# Nappe2_0___Pannelized_3.net
KiCad netlist of a schematic drawn in EAGLE
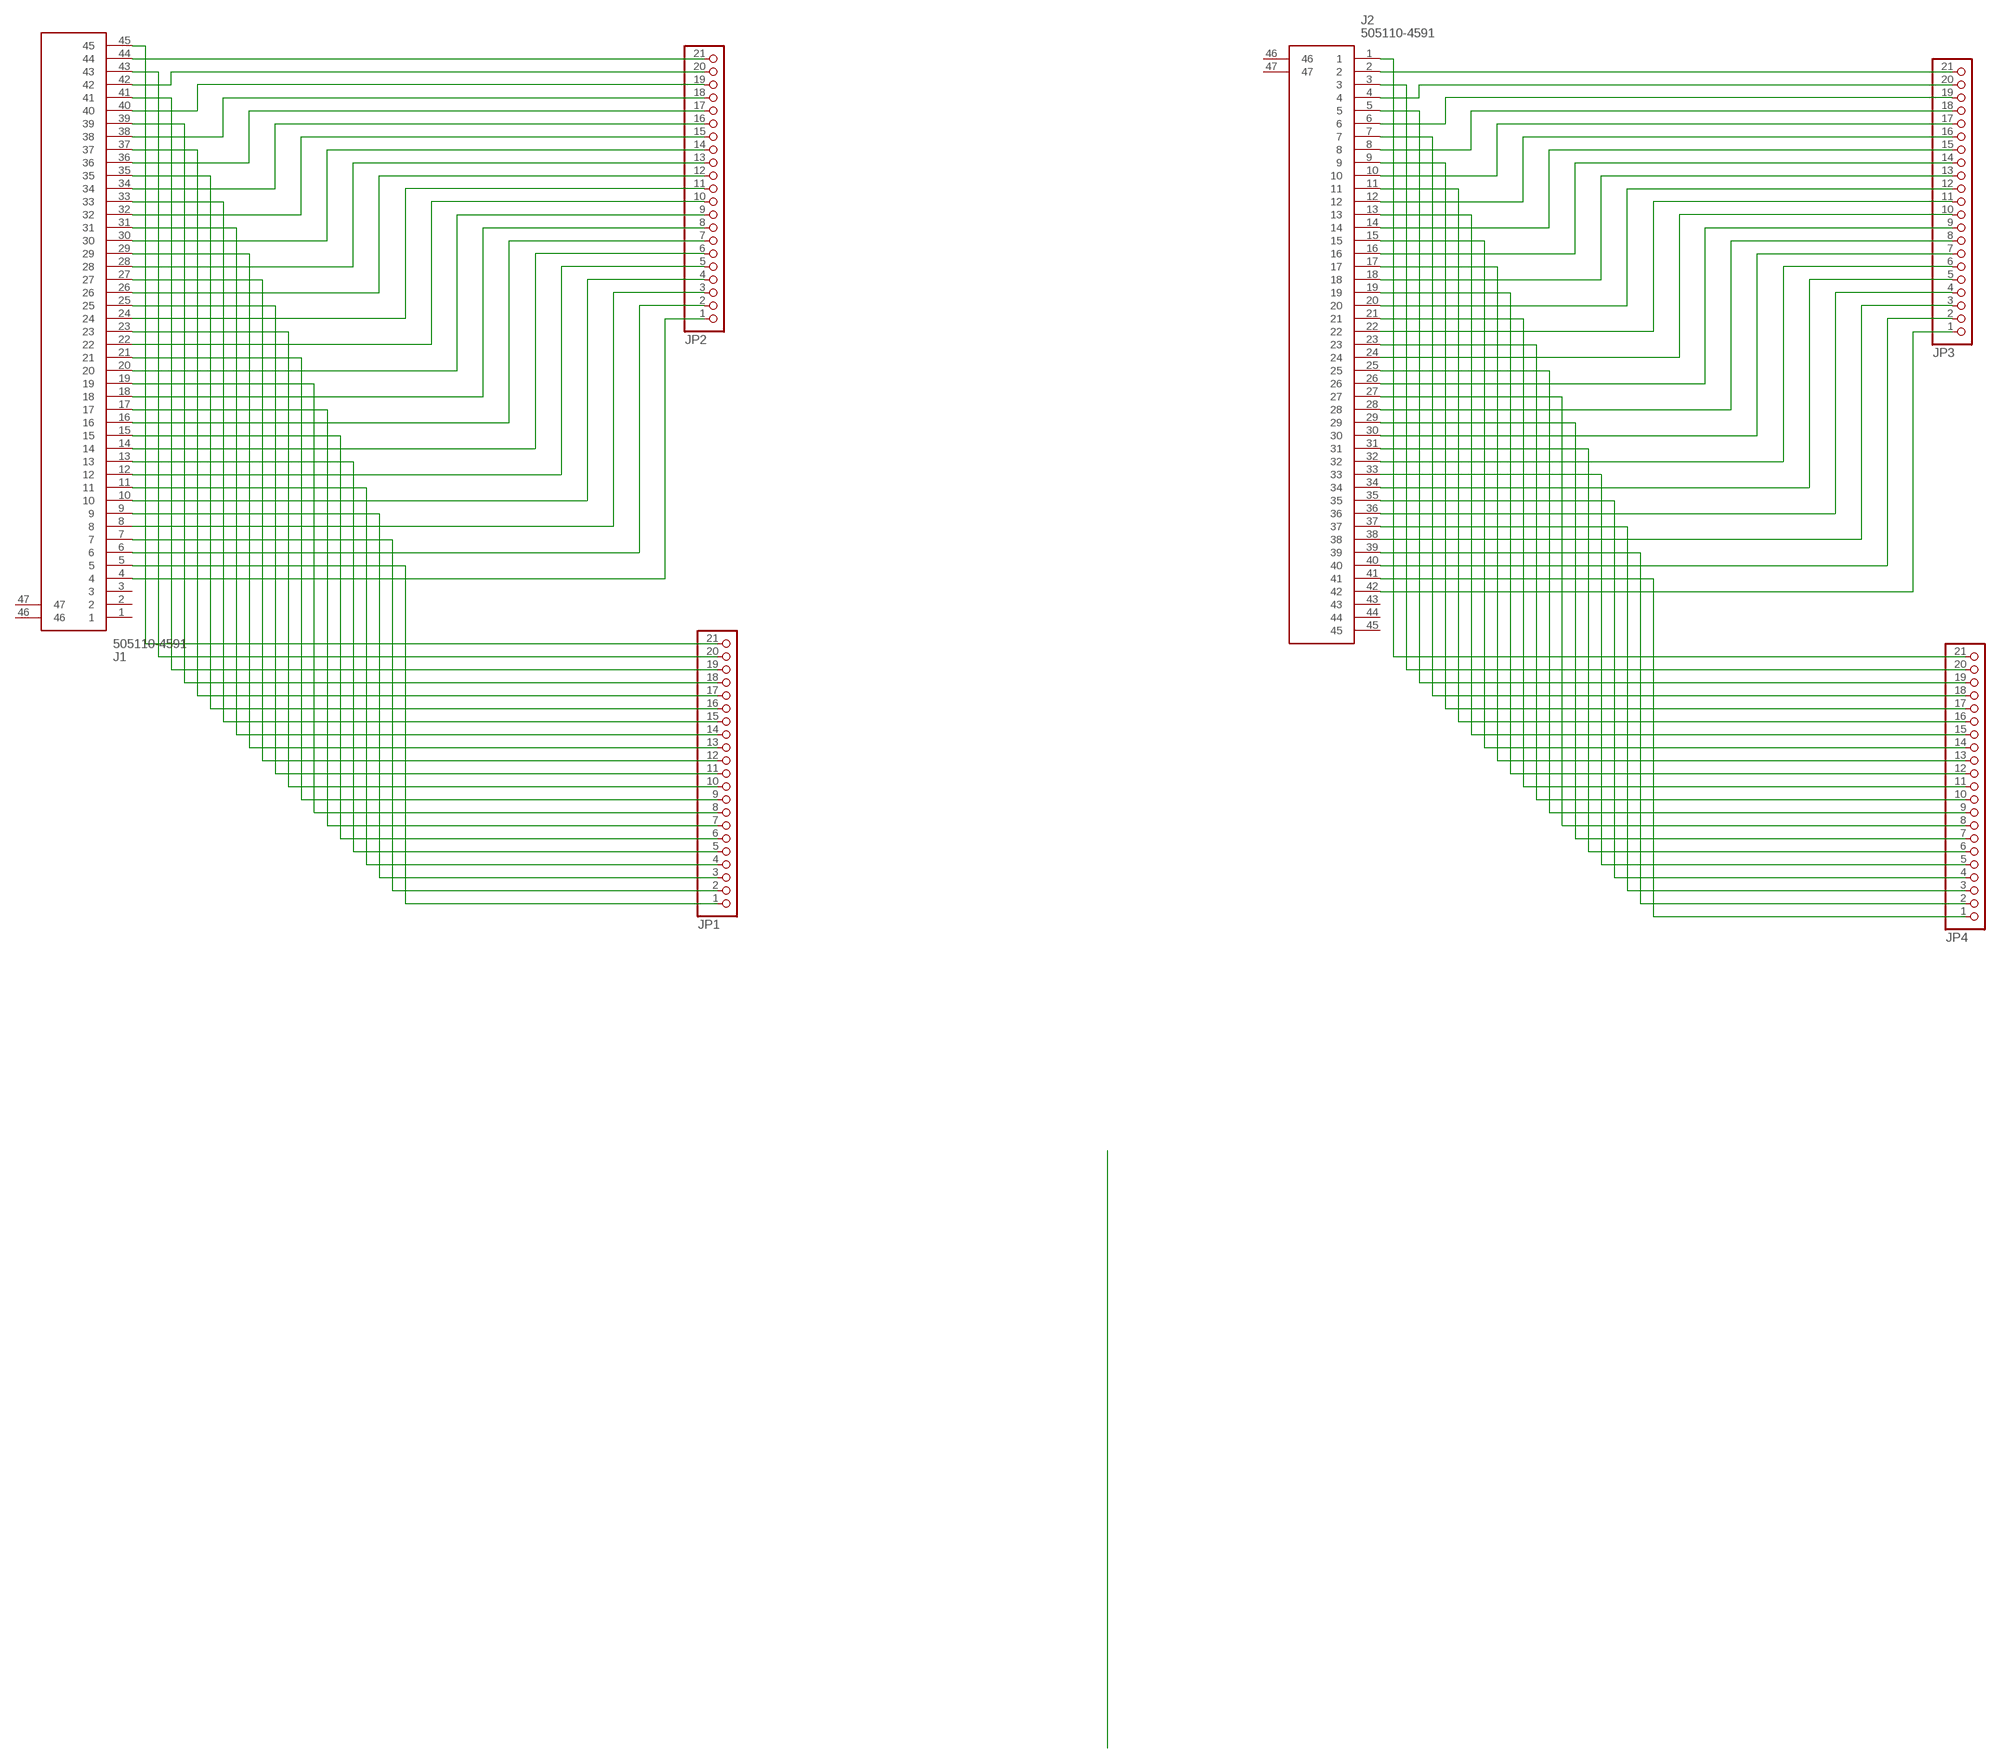
[diagram p0: schematic, sheet 1]

(export (version "E")
  (design (tool "Eeschema 10.0.6"))
  (components
    (comp (ref "J1")
      (value "505110-4591")
      (footprint "eagle-import:5051104591")
      (fields (field (name "MOUSER_PART_NUMBER") "538-505110-4591"))
      (libsource (lib "eagle-import") (part "505110-4591"))
    )
    (comp (ref "J2")
      (value "505110-4591")
      (footprint "eagle-import:5051104591")
      (fields (field (name "MOUSER_PART_NUMBER") "538-505110-4591"))
      (libsource (lib "eagle-import") (part "505110-4591"))
    )
    (comp (ref "JP1")
      (value "PINHD-1X21(2.4)")
      (footprint "eagle-import:1X21(2.4)")
      (libsource (lib "eagle-import") (part "PINHD-1X21(2.4)"))
    )
    (comp (ref "JP2")
      (value "PINHD-1X21(2.4)")
      (footprint "eagle-import:1X21(2.4)")
      (libsource (lib "eagle-import") (part "PINHD-1X21(2.4)"))
    )
    (comp (ref "JP3")
      (value "PINHD-1X21(2.4)")
      (footprint "eagle-import:1X21(2.4)")
      (libsource (lib "eagle-import") (part "PINHD-1X21(2.4)"))
    )
    (comp (ref "JP4")
      (value "PINHD-1X21(2.4)")
      (footprint "eagle-import:1X21(2.4)")
      (libsource (lib "eagle-import") (part "PINHD-1X21(2.4)"))
    )
  )
  (nets
    (net (code "1") (name "Net-(J1-Pad4)") (class "Default")
      (node (ref "J1") (pin "4") (pinfunction "4_4") (pintype "bidirectional"))
      (node (ref "JP2") (pin "1") (pinfunction "1_1") (pintype "passive"))
    )
    (net (code "2") (name "Net-(J1-Pad5)") (class "Default")
      (node (ref "J1") (pin "5") (pinfunction "5_5") (pintype "bidirectional"))
      (node (ref "JP1") (pin "1") (pinfunction "1_1") (pintype "passive"))
    )
    (net (code "3") (name "Net-(J1-Pad6)") (class "Default")
      (node (ref "J1") (pin "6") (pinfunction "6_6") (pintype "bidirectional"))
      (node (ref "JP2") (pin "2") (pinfunction "2_2") (pintype "passive"))
    )
    (net (code "4") (name "Net-(J1-Pad7)") (class "Default")
      (node (ref "J1") (pin "7") (pinfunction "7_7") (pintype "bidirectional"))
      (node (ref "JP1") (pin "2") (pinfunction "2_2") (pintype "passive"))
    )
    (net (code "5") (name "Net-(J1-Pad8)") (class "Default")
      (node (ref "J1") (pin "8") (pinfunction "8_8") (pintype "bidirectional"))
      (node (ref "JP2") (pin "3") (pinfunction "3_3") (pintype "passive"))
    )
    (net (code "6") (name "Net-(J1-Pad9)") (class "Default")
      (node (ref "J1") (pin "9") (pinfunction "9_9") (pintype "bidirectional"))
      (node (ref "JP1") (pin "3") (pinfunction "3_3") (pintype "passive"))
    )
    (net (code "7") (name "Net-(J1-Pad10)") (class "Default")
      (node (ref "J1") (pin "10") (pinfunction "10_10") (pintype "bidirectional"))
      (node (ref "JP2") (pin "4") (pinfunction "4_4") (pintype "passive"))
    )
    (net (code "8") (name "Net-(J1-Pad11)") (class "Default")
      (node (ref "J1") (pin "11") (pinfunction "11_11") (pintype "bidirectional"))
      (node (ref "JP1") (pin "4") (pinfunction "4_4") (pintype "passive"))
    )
    (net (code "9") (name "Net-(J1-Pad12)") (class "Default")
      (node (ref "J1") (pin "12") (pinfunction "12_12") (pintype "bidirectional"))
      (node (ref "JP2") (pin "5") (pinfunction "5_5") (pintype "passive"))
    )
    (net (code "10") (name "Net-(J1-Pad13)") (class "Default")
      (node (ref "J1") (pin "13") (pinfunction "13_13") (pintype "bidirectional"))
      (node (ref "JP1") (pin "5") (pinfunction "5_5") (pintype "passive"))
    )
    (net (code "11") (name "Net-(J1-Pad14)") (class "Default")
      (node (ref "J1") (pin "14") (pinfunction "14_14") (pintype "bidirectional"))
      (node (ref "JP2") (pin "6") (pinfunction "6_6") (pintype "passive"))
    )
    (net (code "12") (name "Net-(J1-Pad15)") (class "Default")
      (node (ref "J1") (pin "15") (pinfunction "15_15") (pintype "bidirectional"))
      (node (ref "JP1") (pin "6") (pinfunction "6_6") (pintype "passive"))
    )
    (net (code "13") (name "Net-(J1-Pad16)") (class "Default")
      (node (ref "J1") (pin "16") (pinfunction "16_16") (pintype "bidirectional"))
      (node (ref "JP2") (pin "7") (pinfunction "7_7") (pintype "passive"))
    )
    (net (code "14") (name "Net-(J1-Pad17)") (class "Default")
      (node (ref "J1") (pin "17") (pinfunction "17_17") (pintype "bidirectional"))
      (node (ref "JP1") (pin "7") (pinfunction "7_7") (pintype "passive"))
    )
    (net (code "15") (name "Net-(J1-Pad18)") (class "Default")
      (node (ref "J1") (pin "18") (pinfunction "18_18") (pintype "bidirectional"))
      (node (ref "JP2") (pin "8") (pinfunction "8_8") (pintype "passive"))
    )
    (net (code "16") (name "Net-(J1-Pad19)") (class "Default")
      (node (ref "J1") (pin "19") (pinfunction "19_19") (pintype "bidirectional"))
      (node (ref "JP1") (pin "8") (pinfunction "8_8") (pintype "passive"))
    )
    (net (code "17") (name "Net-(J1-Pad20)") (class "Default")
      (node (ref "J1") (pin "20") (pinfunction "20_20") (pintype "bidirectional"))
      (node (ref "JP2") (pin "9") (pinfunction "9_9") (pintype "passive"))
    )
    (net (code "18") (name "Net-(J1-Pad21)") (class "Default")
      (node (ref "J1") (pin "21") (pinfunction "21_21") (pintype "bidirectional"))
      (node (ref "JP1") (pin "9") (pinfunction "9_9") (pintype "passive"))
    )
    (net (code "19") (name "Net-(J1-Pad22)") (class "Default")
      (node (ref "J1") (pin "22") (pinfunction "22_22") (pintype "bidirectional"))
      (node (ref "JP2") (pin "10") (pinfunction "10_10") (pintype "passive"))
    )
    (net (code "20") (name "Net-(J1-Pad23)") (class "Default")
      (node (ref "J1") (pin "23") (pinfunction "23_23") (pintype "bidirectional"))
      (node (ref "JP1") (pin "10") (pinfunction "10_10") (pintype "passive"))
    )
    (net (code "21") (name "Net-(J1-Pad24)") (class "Default")
      (node (ref "J1") (pin "24") (pinfunction "24_24") (pintype "bidirectional"))
      (node (ref "JP2") (pin "11") (pinfunction "11_11") (pintype "passive"))
    )
    (net (code "22") (name "Net-(J1-Pad25)") (class "Default")
      (node (ref "J1") (pin "25") (pinfunction "25_25") (pintype "bidirectional"))
      (node (ref "JP1") (pin "11") (pinfunction "11_11") (pintype "passive"))
    )
    (net (code "23") (name "Net-(J1-Pad26)") (class "Default")
      (node (ref "J1") (pin "26") (pinfunction "26_26") (pintype "bidirectional"))
      (node (ref "JP2") (pin "12") (pinfunction "12_12") (pintype "passive"))
    )
    (net (code "24") (name "Net-(J1-Pad27)") (class "Default")
      (node (ref "J1") (pin "27") (pinfunction "27_27") (pintype "bidirectional"))
      (node (ref "JP1") (pin "12") (pinfunction "12_12") (pintype "passive"))
    )
    (net (code "25") (name "Net-(J1-Pad28)") (class "Default")
      (node (ref "J1") (pin "28") (pinfunction "28_28") (pintype "bidirectional"))
      (node (ref "JP2") (pin "13") (pinfunction "13_13") (pintype "passive"))
    )
    (net (code "26") (name "Net-(J1-Pad29)") (class "Default")
      (node (ref "J1") (pin "29") (pinfunction "29_29") (pintype "bidirectional"))
      (node (ref "JP1") (pin "13") (pinfunction "13_13") (pintype "passive"))
    )
    (net (code "27") (name "Net-(J1-Pad30)") (class "Default")
      (node (ref "J1") (pin "30") (pinfunction "30_30") (pintype "bidirectional"))
      (node (ref "JP2") (pin "14") (pinfunction "14_14") (pintype "passive"))
    )
    (net (code "28") (name "Net-(J1-Pad31)") (class "Default")
      (node (ref "J1") (pin "31") (pinfunction "31_31") (pintype "bidirectional"))
      (node (ref "JP1") (pin "14") (pinfunction "14_14") (pintype "passive"))
    )
    (net (code "29") (name "Net-(J1-Pad32)") (class "Default")
      (node (ref "J1") (pin "32") (pinfunction "32_32") (pintype "bidirectional"))
      (node (ref "JP2") (pin "15") (pinfunction "15_15") (pintype "passive"))
    )
    (net (code "30") (name "Net-(J1-Pad33)") (class "Default")
      (node (ref "J1") (pin "33") (pinfunction "33_33") (pintype "bidirectional"))
      (node (ref "JP1") (pin "15") (pinfunction "15_15") (pintype "passive"))
    )
    (net (code "31") (name "Net-(J1-Pad34)") (class "Default")
      (node (ref "J1") (pin "34") (pinfunction "34_34") (pintype "bidirectional"))
      (node (ref "JP2") (pin "16") (pinfunction "16_16") (pintype "passive"))
    )
    (net (code "32") (name "Net-(J1-Pad35)") (class "Default")
      (node (ref "J1") (pin "35") (pinfunction "35_35") (pintype "bidirectional"))
      (node (ref "JP1") (pin "16") (pinfunction "16_16") (pintype "passive"))
    )
    (net (code "33") (name "Net-(J1-Pad36)") (class "Default")
      (node (ref "J1") (pin "36") (pinfunction "36_36") (pintype "bidirectional"))
      (node (ref "JP2") (pin "17") (pinfunction "17_17") (pintype "passive"))
    )
    (net (code "34") (name "Net-(J1-Pad37)") (class "Default")
      (node (ref "J1") (pin "37") (pinfunction "37_37") (pintype "bidirectional"))
      (node (ref "JP1") (pin "17") (pinfunction "17_17") (pintype "passive"))
    )
    (net (code "35") (name "Net-(J1-Pad38)") (class "Default")
      (node (ref "J1") (pin "38") (pinfunction "38_38") (pintype "bidirectional"))
      (node (ref "JP2") (pin "18") (pinfunction "18_18") (pintype "passive"))
    )
    (net (code "36") (name "Net-(J1-Pad39)") (class "Default")
      (node (ref "J1") (pin "39") (pinfunction "39_39") (pintype "bidirectional"))
      (node (ref "JP1") (pin "18") (pinfunction "18_18") (pintype "passive"))
    )
    (net (code "37") (name "Net-(J1-Pad40)") (class "Default")
      (node (ref "J1") (pin "40") (pinfunction "40_40") (pintype "bidirectional"))
      (node (ref "JP2") (pin "19") (pinfunction "19_19") (pintype "passive"))
    )
    (net (code "38") (name "Net-(J1-Pad41)") (class "Default")
      (node (ref "J1") (pin "41") (pinfunction "41_41") (pintype "bidirectional"))
      (node (ref "JP1") (pin "19") (pinfunction "19_19") (pintype "passive"))
    )
    (net (code "39") (name "Net-(J1-Pad42)") (class "Default")
      (node (ref "J1") (pin "42") (pinfunction "42_42") (pintype "bidirectional"))
      (node (ref "JP2") (pin "20") (pinfunction "20_20") (pintype "passive"))
    )
    (net (code "40") (name "Net-(J1-Pad43)") (class "Default")
      (node (ref "J1") (pin "43") (pinfunction "43_43") (pintype "bidirectional"))
      (node (ref "JP1") (pin "20") (pinfunction "20_20") (pintype "passive"))
    )
    (net (code "41") (name "Net-(J1-Pad44)") (class "Default")
      (node (ref "J1") (pin "44") (pinfunction "44_44") (pintype "bidirectional"))
      (node (ref "JP2") (pin "21") (pinfunction "21_21") (pintype "passive"))
    )
    (net (code "42") (name "Net-(J1-Pad45)") (class "Default")
      (node (ref "J1") (pin "45") (pinfunction "45_45") (pintype "bidirectional"))
      (node (ref "JP1") (pin "21") (pinfunction "21_21") (pintype "passive"))
    )
    (net (code "43") (name "Net-(J2-Pad1)") (class "Default")
      (node (ref "J2") (pin "1") (pinfunction "1_1") (pintype "bidirectional"))
      (node (ref "JP4") (pin "21") (pinfunction "21_21") (pintype "passive"))
    )
    (net (code "44") (name "Net-(J2-Pad2)") (class "Default")
      (node (ref "J2") (pin "2") (pinfunction "2_2") (pintype "bidirectional"))
      (node (ref "JP3") (pin "21") (pinfunction "21_21") (pintype "passive"))
    )
    (net (code "45") (name "Net-(J2-Pad3)") (class "Default")
      (node (ref "J2") (pin "3") (pinfunction "3_3") (pintype "bidirectional"))
      (node (ref "JP4") (pin "20") (pinfunction "20_20") (pintype "passive"))
    )
    (net (code "46") (name "Net-(J2-Pad4)") (class "Default")
      (node (ref "J2") (pin "4") (pinfunction "4_4") (pintype "bidirectional"))
      (node (ref "JP3") (pin "20") (pinfunction "20_20") (pintype "passive"))
    )
    (net (code "47") (name "Net-(J2-Pad5)") (class "Default")
      (node (ref "J2") (pin "5") (pinfunction "5_5") (pintype "bidirectional"))
      (node (ref "JP4") (pin "19") (pinfunction "19_19") (pintype "passive"))
    )
    (net (code "48") (name "Net-(J2-Pad6)") (class "Default")
      (node (ref "J2") (pin "6") (pinfunction "6_6") (pintype "bidirectional"))
      (node (ref "JP3") (pin "19") (pinfunction "19_19") (pintype "passive"))
    )
    (net (code "49") (name "Net-(J2-Pad7)") (class "Default")
      (node (ref "J2") (pin "7") (pinfunction "7_7") (pintype "bidirectional"))
      (node (ref "JP4") (pin "18") (pinfunction "18_18") (pintype "passive"))
    )
    (net (code "50") (name "Net-(J2-Pad8)") (class "Default")
      (node (ref "J2") (pin "8") (pinfunction "8_8") (pintype "bidirectional"))
      (node (ref "JP3") (pin "18") (pinfunction "18_18") (pintype "passive"))
    )
    (net (code "51") (name "Net-(J2-Pad9)") (class "Default")
      (node (ref "J2") (pin "9") (pinfunction "9_9") (pintype "bidirectional"))
      (node (ref "JP4") (pin "17") (pinfunction "17_17") (pintype "passive"))
    )
    (net (code "52") (name "Net-(J2-Pad10)") (class "Default")
      (node (ref "J2") (pin "10") (pinfunction "10_10") (pintype "bidirectional"))
      (node (ref "JP3") (pin "17") (pinfunction "17_17") (pintype "passive"))
    )
    (net (code "53") (name "Net-(J2-Pad11)") (class "Default")
      (node (ref "J2") (pin "11") (pinfunction "11_11") (pintype "bidirectional"))
      (node (ref "JP4") (pin "16") (pinfunction "16_16") (pintype "passive"))
    )
    (net (code "54") (name "Net-(J2-Pad12)") (class "Default")
      (node (ref "J2") (pin "12") (pinfunction "12_12") (pintype "bidirectional"))
      (node (ref "JP3") (pin "16") (pinfunction "16_16") (pintype "passive"))
    )
    (net (code "55") (name "Net-(J2-Pad13)") (class "Default")
      (node (ref "J2") (pin "13") (pinfunction "13_13") (pintype "bidirectional"))
      (node (ref "JP4") (pin "15") (pinfunction "15_15") (pintype "passive"))
    )
    (net (code "56") (name "Net-(J2-Pad14)") (class "Default")
      (node (ref "J2") (pin "14") (pinfunction "14_14") (pintype "bidirectional"))
      (node (ref "JP3") (pin "15") (pinfunction "15_15") (pintype "passive"))
    )
    (net (code "57") (name "Net-(J2-Pad15)") (class "Default")
      (node (ref "J2") (pin "15") (pinfunction "15_15") (pintype "bidirectional"))
      (node (ref "JP4") (pin "14") (pinfunction "14_14") (pintype "passive"))
    )
    (net (code "58") (name "Net-(J2-Pad16)") (class "Default")
      (node (ref "J2") (pin "16") (pinfunction "16_16") (pintype "bidirectional"))
      (node (ref "JP3") (pin "14") (pinfunction "14_14") (pintype "passive"))
    )
    (net (code "59") (name "Net-(J2-Pad17)") (class "Default")
      (node (ref "J2") (pin "17") (pinfunction "17_17") (pintype "bidirectional"))
      (node (ref "JP4") (pin "13") (pinfunction "13_13") (pintype "passive"))
    )
    (net (code "60") (name "Net-(J2-Pad18)") (class "Default")
      (node (ref "J2") (pin "18") (pinfunction "18_18") (pintype "bidirectional"))
      (node (ref "JP3") (pin "13") (pinfunction "13_13") (pintype "passive"))
    )
    (net (code "61") (name "Net-(J2-Pad19)") (class "Default")
      (node (ref "J2") (pin "19") (pinfunction "19_19") (pintype "bidirectional"))
      (node (ref "JP4") (pin "12") (pinfunction "12_12") (pintype "passive"))
    )
    (net (code "62") (name "Net-(J2-Pad20)") (class "Default")
      (node (ref "J2") (pin "20") (pinfunction "20_20") (pintype "bidirectional"))
      (node (ref "JP3") (pin "12") (pinfunction "12_12") (pintype "passive"))
    )
    (net (code "63") (name "Net-(J2-Pad21)") (class "Default")
      (node (ref "J2") (pin "21") (pinfunction "21_21") (pintype "bidirectional"))
      (node (ref "JP4") (pin "11") (pinfunction "11_11") (pintype "passive"))
    )
    (net (code "64") (name "Net-(J2-Pad22)") (class "Default")
      (node (ref "J2") (pin "22") (pinfunction "22_22") (pintype "bidirectional"))
      (node (ref "JP3") (pin "11") (pinfunction "11_11") (pintype "passive"))
    )
    (net (code "65") (name "Net-(J2-Pad23)") (class "Default")
      (node (ref "J2") (pin "23") (pinfunction "23_23") (pintype "bidirectional"))
      (node (ref "JP4") (pin "10") (pinfunction "10_10") (pintype "passive"))
    )
    (net (code "66") (name "Net-(J2-Pad24)") (class "Default")
      (node (ref "J2") (pin "24") (pinfunction "24_24") (pintype "bidirectional"))
      (node (ref "JP3") (pin "10") (pinfunction "10_10") (pintype "passive"))
    )
    (net (code "67") (name "Net-(J2-Pad25)") (class "Default")
      (node (ref "J2") (pin "25") (pinfunction "25_25") (pintype "bidirectional"))
      (node (ref "JP4") (pin "9") (pinfunction "9_9") (pintype "passive"))
    )
    (net (code "68") (name "Net-(J2-Pad26)") (class "Default")
      (node (ref "J2") (pin "26") (pinfunction "26_26") (pintype "bidirectional"))
      (node (ref "JP3") (pin "9") (pinfunction "9_9") (pintype "passive"))
    )
    (net (code "69") (name "Net-(J2-Pad27)") (class "Default")
      (node (ref "J2") (pin "27") (pinfunction "27_27") (pintype "bidirectional"))
      (node (ref "JP4") (pin "8") (pinfunction "8_8") (pintype "passive"))
    )
    (net (code "70") (name "Net-(J2-Pad28)") (class "Default")
      (node (ref "J2") (pin "28") (pinfunction "28_28") (pintype "bidirectional"))
      (node (ref "JP3") (pin "8") (pinfunction "8_8") (pintype "passive"))
    )
    (net (code "71") (name "Net-(J2-Pad29)") (class "Default")
      (node (ref "J2") (pin "29") (pinfunction "29_29") (pintype "bidirectional"))
      (node (ref "JP4") (pin "7") (pinfunction "7_7") (pintype "passive"))
    )
    (net (code "72") (name "Net-(J2-Pad30)") (class "Default")
      (node (ref "J2") (pin "30") (pinfunction "30_30") (pintype "bidirectional"))
      (node (ref "JP3") (pin "7") (pinfunction "7_7") (pintype "passive"))
    )
    (net (code "73") (name "Net-(J2-Pad31)") (class "Default")
      (node (ref "J2") (pin "31") (pinfunction "31_31") (pintype "bidirectional"))
      (node (ref "JP4") (pin "6") (pinfunction "6_6") (pintype "passive"))
    )
    (net (code "74") (name "Net-(J2-Pad32)") (class "Default")
      (node (ref "J2") (pin "32") (pinfunction "32_32") (pintype "bidirectional"))
      (node (ref "JP3") (pin "6") (pinfunction "6_6") (pintype "passive"))
    )
    (net (code "75") (name "Net-(J2-Pad33)") (class "Default")
      (node (ref "J2") (pin "33") (pinfunction "33_33") (pintype "bidirectional"))
      (node (ref "JP4") (pin "5") (pinfunction "5_5") (pintype "passive"))
    )
    (net (code "76") (name "Net-(J2-Pad34)") (class "Default")
      (node (ref "J2") (pin "34") (pinfunction "34_34") (pintype "bidirectional"))
      (node (ref "JP3") (pin "5") (pinfunction "5_5") (pintype "passive"))
    )
    (net (code "77") (name "Net-(J2-Pad35)") (class "Default")
      (node (ref "J2") (pin "35") (pinfunction "35_35") (pintype "bidirectional"))
      (node (ref "JP4") (pin "4") (pinfunction "4_4") (pintype "passive"))
    )
    (net (code "78") (name "Net-(J2-Pad36)") (class "Default")
      (node (ref "J2") (pin "36") (pinfunction "36_36") (pintype "bidirectional"))
      (node (ref "JP3") (pin "4") (pinfunction "4_4") (pintype "passive"))
    )
    (net (code "79") (name "Net-(J2-Pad37)") (class "Default")
      (node (ref "J2") (pin "37") (pinfunction "37_37") (pintype "bidirectional"))
      (node (ref "JP4") (pin "3") (pinfunction "3_3") (pintype "passive"))
    )
    (net (code "80") (name "Net-(J2-Pad38)") (class "Default")
      (node (ref "J2") (pin "38") (pinfunction "38_38") (pintype "bidirectional"))
      (node (ref "JP3") (pin "3") (pinfunction "3_3") (pintype "passive"))
    )
    (net (code "81") (name "Net-(J2-Pad39)") (class "Default")
      (node (ref "J2") (pin "39") (pinfunction "39_39") (pintype "bidirectional"))
      (node (ref "JP4") (pin "2") (pinfunction "2_2") (pintype "passive"))
    )
    (net (code "82") (name "Net-(J2-Pad40)") (class "Default")
      (node (ref "J2") (pin "40") (pinfunction "40_40") (pintype "bidirectional"))
      (node (ref "JP3") (pin "2") (pinfunction "2_2") (pintype "passive"))
    )
    (net (code "83") (name "Net-(J2-Pad41)") (class "Default")
      (node (ref "J2") (pin "41") (pinfunction "41_41") (pintype "bidirectional"))
      (node (ref "JP4") (pin "1") (pinfunction "1_1") (pintype "passive"))
    )
    (net (code "84") (name "Net-(J2-Pad42)") (class "Default")
      (node (ref "J2") (pin "42") (pinfunction "42_42") (pintype "bidirectional"))
      (node (ref "JP3") (pin "1") (pinfunction "1_1") (pintype "passive"))
    )
    (net (code "85") (name "unconnected-(J1-Pad1)") (class "Default")
      (node (ref "J1") (pin "1") (pinfunction "1_1") (pintype "bidirectional"))
    )
    (net (code "86") (name "unconnected-(J1-Pad2)") (class "Default")
      (node (ref "J1") (pin "2") (pinfunction "2_2") (pintype "bidirectional"))
    )
    (net (code "87") (name "unconnected-(J1-Pad3)") (class "Default")
      (node (ref "J1") (pin "3") (pinfunction "3_3") (pintype "bidirectional"))
    )
    (net (code "88") (name "unconnected-(J1-Pad46)") (class "Default")
      (node (ref "J1") (pin "46") (pinfunction "46_46") (pintype "bidirectional"))
    )
    (net (code "89") (name "unconnected-(J1-Pad47)") (class "Default")
      (node (ref "J1") (pin "47") (pinfunction "47_47") (pintype "bidirectional"))
    )
    (net (code "90") (name "unconnected-(J2-Pad43)") (class "Default")
      (node (ref "J2") (pin "43") (pinfunction "43_43") (pintype "bidirectional"))
    )
    (net (code "91") (name "unconnected-(J2-Pad44)") (class "Default")
      (node (ref "J2") (pin "44") (pinfunction "44_44") (pintype "bidirectional"))
    )
    (net (code "92") (name "unconnected-(J2-Pad45)") (class "Default")
      (node (ref "J2") (pin "45") (pinfunction "45_45") (pintype "bidirectional"))
    )
    (net (code "93") (name "unconnected-(J2-Pad46)") (class "Default")
      (node (ref "J2") (pin "46") (pinfunction "46_46") (pintype "bidirectional"))
    )
    (net (code "94") (name "unconnected-(J2-Pad47)") (class "Default")
      (node (ref "J2") (pin "47") (pinfunction "47_47") (pintype "bidirectional"))
    )
  )
)
